# VIP.net
KiCad netlist of a schematic drawn in EAGLE
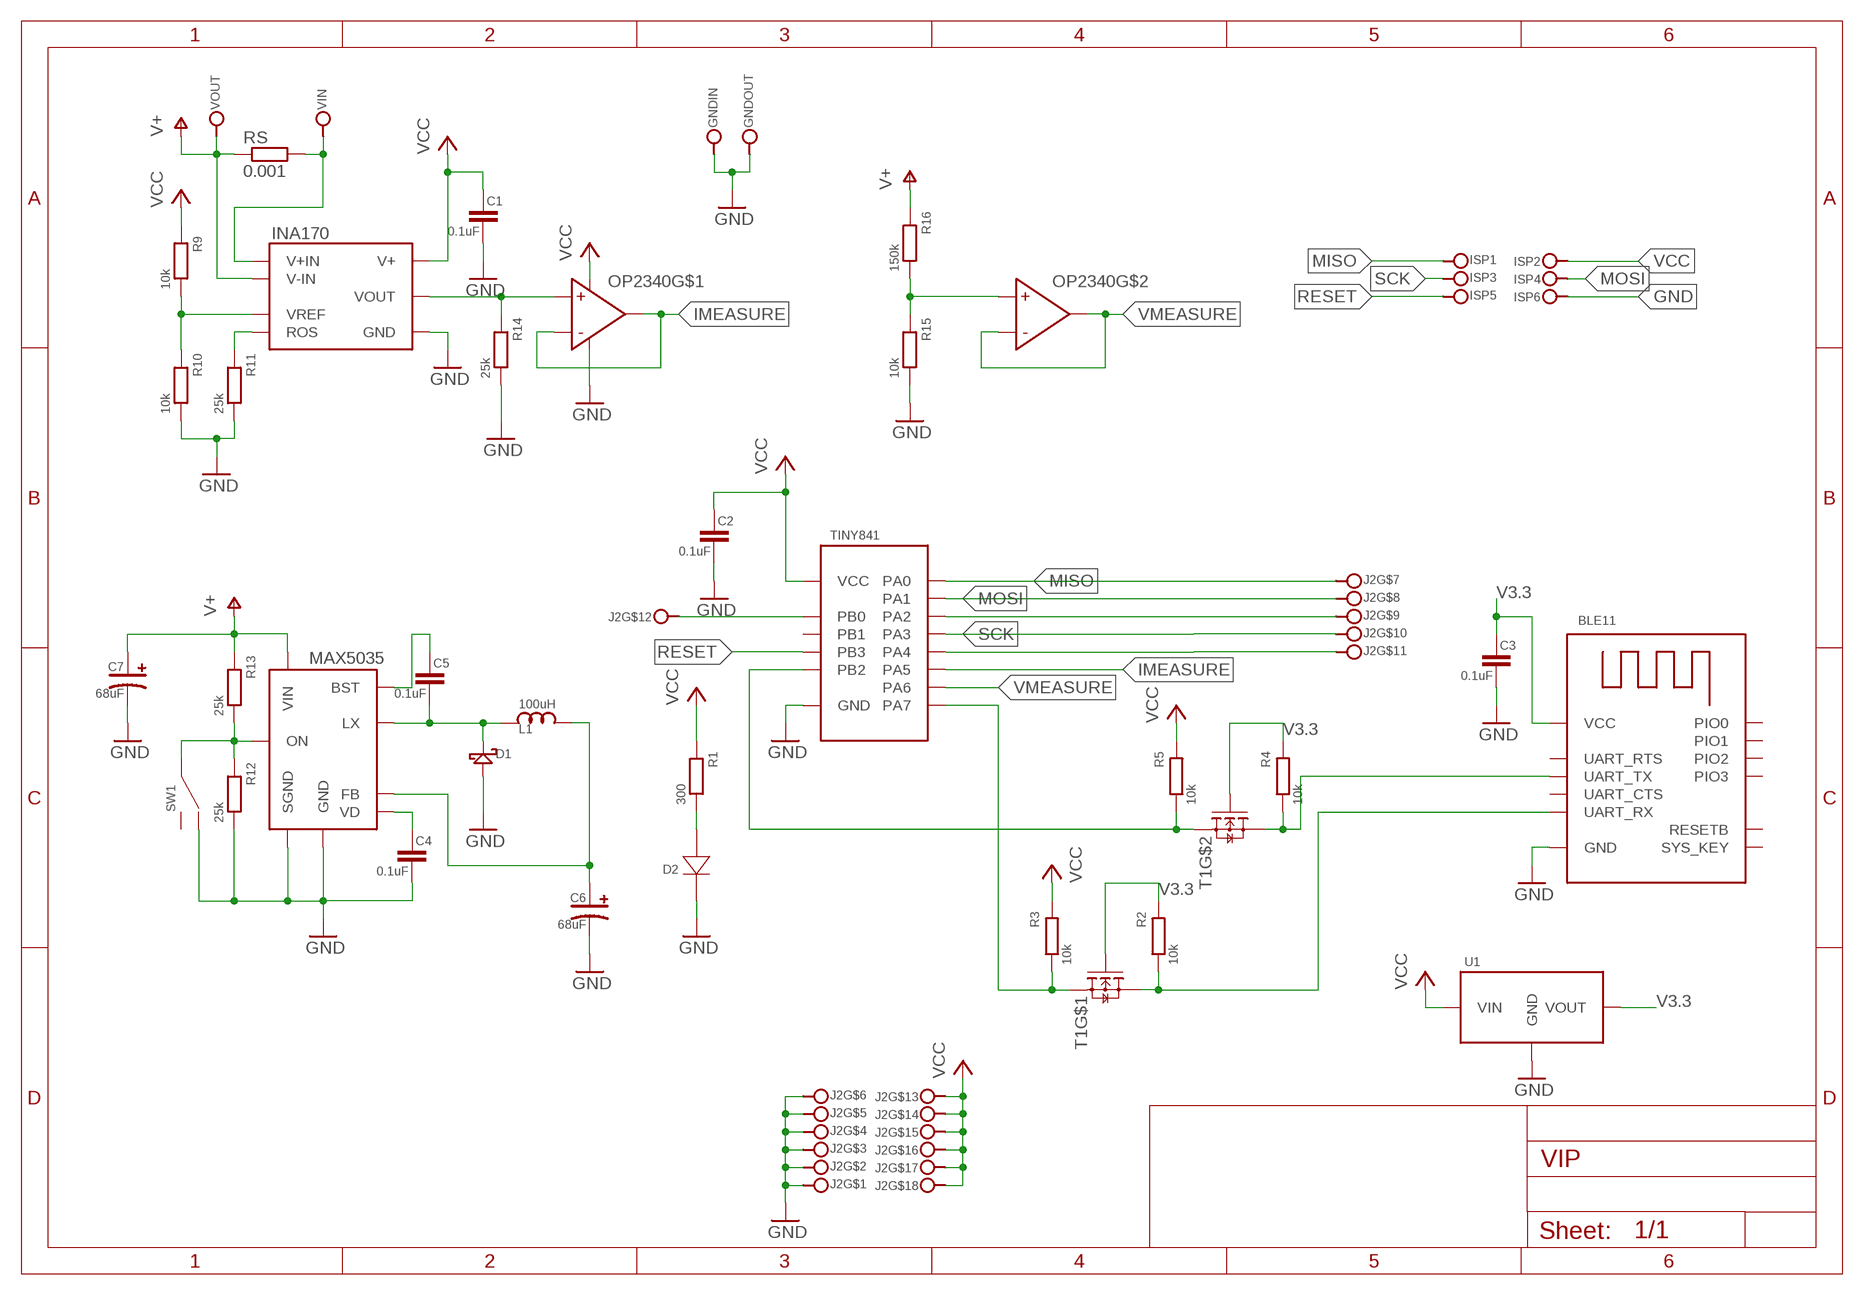
[diagram p0: schematic, sheet 1]

(export (version "E")
  (design (tool "Eeschema 10.0.6"))
  (components
    (comp (ref "BLE11")
      (value "HM-17BLE")
      (footprint "eagle-import:HM17BLE")
      (libsource (lib "eagle-import") (part "HM-17BLE"))
    )
    (comp (ref "C1")
      (value "0.1uF")
      (footprint "eagle-import:0603L")
      (libsource (lib "eagle-import") (part "C_SMD"))
    )
    (comp (ref "C2")
      (value "0.1uF")
      (footprint "eagle-import:0603L")
      (libsource (lib "eagle-import") (part "C_SMD"))
    )
    (comp (ref "C3")
      (value "0.1uF")
      (footprint "eagle-import:0603L")
      (libsource (lib "eagle-import") (part "C_SMD"))
    )
    (comp (ref "C4")
      (value "0.1uF")
      (footprint "eagle-import:0603L")
      (libsource (lib "eagle-import") (part "C_SMD"))
    )
    (comp (ref "C5")
      (value "0.1uF")
      (footprint "eagle-import:0603L")
      (libsource (lib "eagle-import") (part "C_SMD"))
    )
    (comp (ref "C6")
      (value "68uF")
      (footprint "eagle-import:RAD6.3MM")
      (libsource (lib "eagle-import") (part "ECAP_SMD6.3MM"))
    )
    (comp (ref "C7")
      (value "68uF")
      (footprint "eagle-import:RAD12.5MM")
      (libsource (lib "eagle-import") (part "ECAP_SMD12.5MM"))
    )
    (comp (ref "D1")
      (value "SCHOTTKY")
      (footprint "eagle-import:DO-214AA")
      (libsource (lib "eagle-import") (part "SCHOTTKY"))
    )
    (comp (ref "D2")
      (value "SINGLELEDKP-3216SRC-PRV")
      (footprint "eagle-import:LED3.2X1.6MM")
      (libsource (lib "eagle-import") (part "SINGLELEDKP-3216SRC-PRV"))
    )
    (comp (ref "GNDIN")
      (value "POWERTAB")
      (footprint "eagle-import:POWER8X10MM")
      (libsource (lib "eagle-import") (part "POWERTAB"))
    )
    (comp (ref "GNDOUT")
      (value "POWERTAB")
      (footprint "eagle-import:POWER8X10MM")
      (libsource (lib "eagle-import") (part "POWERTAB"))
    )
    (comp (ref "INA170")
      (value "INA170")
      (footprint "eagle-import:INA170")
      (libsource (lib "eagle-import") (part "INA170"))
    )
    (comp (ref "ISP")
      (value "CON254_6WAY254-2X3-EDGE")
      (footprint "eagle-import:CON254MM08_2X3_EDGE")
      (libsource (lib "eagle-import") (part "CON254_6WAY254-2X3-EDGE"))
    )
    (comp (ref "J2")
      (value "CON254_18WAY3X6")
      (footprint "eagle-import:CON254MM08_3X6")
      (libsource (lib "eagle-import") (part "CON254_18WAY3X6"))
    )
    (comp (ref "L1")
      (value "100uH")
      (footprint "eagle-import:SRN8040")
      (libsource (lib "eagle-import") (part "L_SMD8040"))
    )
    (comp (ref "MAX5035")
      (value "MAX5035")
      (footprint "eagle-import:NSOIC-8")
      (libsource (lib "eagle-import") (part "MAX5035"))
    )
    (comp (ref "OP2340")
      (value "OPA2340")
      (footprint "eagle-import:SO-8")
      (libsource (lib "eagle-import") (part "OPA2340"))
    )
    (comp (ref "R1")
      (value "300")
      (footprint "eagle-import:0603L")
      (libsource (lib "eagle-import") (part "R_SMD"))
    )
    (comp (ref "R2")
      (value "10k")
      (footprint "eagle-import:0603L")
      (libsource (lib "eagle-import") (part "R_SMD"))
    )
    (comp (ref "R3")
      (value "10k")
      (footprint "eagle-import:0603L")
      (libsource (lib "eagle-import") (part "R_SMD"))
    )
    (comp (ref "R4")
      (value "10k")
      (footprint "eagle-import:0603L")
      (libsource (lib "eagle-import") (part "R_SMD"))
    )
    (comp (ref "R5")
      (value "10k")
      (footprint "eagle-import:0603L")
      (libsource (lib "eagle-import") (part "R_SMD"))
    )
    (comp (ref "R9")
      (value "10k")
      (footprint "eagle-import:0603L")
      (libsource (lib "eagle-import") (part "R_SMD"))
    )
    (comp (ref "R10")
      (value "10k")
      (footprint "eagle-import:0603L")
      (libsource (lib "eagle-import") (part "R_SMD"))
    )
    (comp (ref "R11")
      (value "25k")
      (footprint "eagle-import:0603L")
      (libsource (lib "eagle-import") (part "R_SMD"))
    )
    (comp (ref "R12")
      (value "25k")
      (footprint "eagle-import:0603L")
      (libsource (lib "eagle-import") (part "R_SMD"))
    )
    (comp (ref "R13")
      (value "25k")
      (footprint "eagle-import:0603L")
      (libsource (lib "eagle-import") (part "R_SMD"))
    )
    (comp (ref "R14")
      (value "25k")
      (footprint "eagle-import:0603L")
      (libsource (lib "eagle-import") (part "R_SMD"))
    )
    (comp (ref "R15")
      (value "10k")
      (footprint "eagle-import:0603L")
      (libsource (lib "eagle-import") (part "R_SMD"))
    )
    (comp (ref "R16")
      (value "150k")
      (footprint "eagle-import:0603L")
      (libsource (lib "eagle-import") (part "R_SMD"))
    )
    (comp (ref "RS")
      (value "0.001")
      (footprint "eagle-import:3921[1052METRIC]")
      (libsource (lib "eagle-import") (part "R-EU_3921[1052METRIC]"))
    )
    (comp (ref "SW1")
      (value "SWITCH-1P2T")
      (footprint "eagle-import:JS102011")
      (libsource (lib "eagle-import") (part "SWITCH-1P2T"))
    )
    (comp (ref "T1")
      (value "2N7002")
      (footprint "eagle-import:SOT-563")
      (libsource (lib "eagle-import") (part "2N7002"))
    )
    (comp (ref "TINY841")
      (value "ATTINY841")
      (footprint "eagle-import:SOIC14")
      (libsource (lib "eagle-import") (part "ATTINY841"))
    )
    (comp (ref "U1")
      (value "L78L33A")
      (footprint "eagle-import:SOT-89")
      (libsource (lib "eagle-import") (part "L78L33A"))
    )
    (comp (ref "VIN")
      (value "POWERTAB")
      (footprint "eagle-import:POWER8X10MM")
      (libsource (lib "eagle-import") (part "POWERTAB"))
    )
    (comp (ref "VOUT")
      (value "POWERTAB")
      (footprint "eagle-import:POWER8X10MM")
      (libsource (lib "eagle-import") (part "POWERTAB"))
    )
  )
  (nets
    (net (code "1") (name "/V3.3") (class "Default")
      (node (ref "BLE11") (pin "P$9") (pinfunction "VCC_P$9") (pintype "bidirectional"))
      (node (ref "C3") (pin "P$1") (pinfunction "P$1_P$1") (pintype "bidirectional"))
      (node (ref "R2") (pin "P$1") (pinfunction "P$1_P$1") (pintype "bidirectional"))
      (node (ref "R4") (pin "P$1") (pinfunction "P$1_P$1") (pintype "bidirectional"))
      (node (ref "T1") (pin "P$2") (pinfunction "G_P$2") (pintype "bidirectional"))
      (node (ref "T1") (pin "P$5") (pinfunction "G_P$5") (pintype "bidirectional"))
      (node (ref "U1") (pin "P$1") (pinfunction "VOUT_P$1") (pintype "bidirectional"))
    )
    (net (code "2") (name "GND") (class "Default")
      (node (ref "BLE11") (pin "P$12") (pinfunction "GND_P$12") (pintype "bidirectional"))
      (node (ref "C1") (pin "P$2") (pinfunction "P$2_P$2") (pintype "bidirectional"))
      (node (ref "C2") (pin "P$2") (pinfunction "P$2_P$2") (pintype "bidirectional"))
      (node (ref "C3") (pin "P$2") (pinfunction "P$2_P$2") (pintype "bidirectional"))
      (node (ref "C4") (pin "P$2") (pinfunction "P$2_P$2") (pintype "bidirectional"))
      (node (ref "C6") (pin "P$2") (pinfunction "P$2_P$2") (pintype "bidirectional"))
      (node (ref "C7") (pin "P$2") (pinfunction "P$2_P$2") (pintype "bidirectional"))
      (node (ref "D1") (pin "P$2") (pinfunction "A_P$2") (pintype "bidirectional"))
      (node (ref "D2") (pin "P$2") (pinfunction "K_P$2") (pintype "bidirectional"))
      (node (ref "GNDIN") (pin "P$1") (pinfunction "J$1_P$1") (pintype "bidirectional"))
      (node (ref "GNDOUT") (pin "P$1") (pinfunction "J$1_P$1") (pintype "bidirectional"))
      (node (ref "INA170") (pin "P$4") (pinfunction "GND_P$4") (pintype "bidirectional"))
      (node (ref "ISP") (pin "P$6") (pinfunction "J$1_P$6") (pintype "bidirectional"))
      (node (ref "J2") (pin "P$1") (pinfunction "J$1_P$1") (pintype "bidirectional"))
      (node (ref "J2") (pin "P$2") (pinfunction "J$1_P$2") (pintype "bidirectional"))
      (node (ref "J2") (pin "P$3") (pinfunction "J$1_P$3") (pintype "bidirectional"))
      (node (ref "J2") (pin "P$4") (pinfunction "J$1_P$4") (pintype "bidirectional"))
      (node (ref "J2") (pin "P$5") (pinfunction "J$1_P$5") (pintype "bidirectional"))
      (node (ref "J2") (pin "P$6") (pinfunction "J$1_P$6") (pintype "bidirectional"))
      (node (ref "MAX5035") (pin "P$3") (pinfunction "SGND_P$3") (pintype "bidirectional"))
      (node (ref "MAX5035") (pin "P$6") (pinfunction "GND_P$6") (pintype "bidirectional"))
      (node (ref "OP2340") (pin "P$4") (pinfunction "V-_P$4") (pintype "power_in"))
      (node (ref "R10") (pin "P$2") (pinfunction "P$2_P$2") (pintype "bidirectional"))
      (node (ref "R11") (pin "P$2") (pinfunction "P$2_P$2") (pintype "bidirectional"))
      (node (ref "R12") (pin "P$2") (pinfunction "P$2_P$2") (pintype "bidirectional"))
      (node (ref "R14") (pin "P$2") (pinfunction "P$2_P$2") (pintype "bidirectional"))
      (node (ref "R15") (pin "P$2") (pinfunction "P$2_P$2") (pintype "bidirectional"))
      (node (ref "SW1") (pin "P$1") (pinfunction "P$2_P$1") (pintype "bidirectional"))
      (node (ref "TINY841") (pin "P$14") (pinfunction "GND_P$14") (pintype "bidirectional"))
      (node (ref "U1") (pin "P$2") (pinfunction "GND_P$2") (pintype "bidirectional"))
    )
    (net (code "3") (name "IMEASURE") (class "Default")
      (node (ref "OP2340") (pin "P$1") (pinfunction "OUT_P$1") (pintype "bidirectional"))
      (node (ref "OP2340") (pin "P$2") (pinfunction "IN-_P$2") (pintype "bidirectional"))
      (node (ref "TINY841") (pin "P$8") (pinfunction "PA5_P$8") (pintype "bidirectional"))
    )
    (net (code "4") (name "MISO") (class "Default")
      (node (ref "ISP") (pin "P$1") (pinfunction "J$1_P$1") (pintype "bidirectional"))
      (node (ref "J2") (pin "P$7") (pinfunction "J$1_P$7") (pintype "bidirectional"))
      (node (ref "TINY841") (pin "P$13") (pinfunction "PA0_P$13") (pintype "bidirectional"))
    )
    (net (code "5") (name "MOSI") (class "Default")
      (node (ref "ISP") (pin "P$4") (pinfunction "J$1_P$4") (pintype "bidirectional"))
      (node (ref "J2") (pin "P$8") (pinfunction "J$1_P$8") (pintype "bidirectional"))
      (node (ref "TINY841") (pin "P$12") (pinfunction "PA1_P$12") (pintype "bidirectional"))
    )
    (net (code "6") (name "Net-(BLE11-UART_RX)") (class "Default")
      (node (ref "BLE11") (pin "P$4") (pinfunction "UART_RX_P$4") (pintype "bidirectional"))
      (node (ref "R2") (pin "P$2") (pinfunction "P$2_P$2") (pintype "bidirectional"))
      (node (ref "T1") (pin "P$3") (pinfunction "D_P$3") (pintype "bidirectional"))
    )
    (net (code "7") (name "Net-(BLE11-UART_TX)") (class "Default")
      (node (ref "BLE11") (pin "P$2") (pinfunction "UART_TX_P$2") (pintype "bidirectional"))
      (node (ref "R4") (pin "P$2") (pinfunction "P$2_P$2") (pintype "bidirectional"))
      (node (ref "T1") (pin "P$6") (pinfunction "D_P$6") (pintype "bidirectional"))
    )
    (net (code "8") (name "Net-(D1-C)") (class "Default")
      (node (ref "C5") (pin "P$2") (pinfunction "P$2_P$2") (pintype "bidirectional"))
      (node (ref "D1") (pin "P$1") (pinfunction "C_P$1") (pintype "bidirectional"))
      (node (ref "L1") (pin "P$1") (pinfunction "P$1_P$1") (pintype "bidirectional"))
      (node (ref "MAX5035") (pin "P$8") (pinfunction "LX_P$8") (pintype "bidirectional"))
    )
    (net (code "9") (name "Net-(D2-A)") (class "Default")
      (node (ref "D2") (pin "P$1") (pinfunction "A_P$1") (pintype "bidirectional"))
      (node (ref "R1") (pin "P$2") (pinfunction "P$2_P$2") (pintype "bidirectional"))
    )
    (net (code "10") (name "Net-(INA170-ROS)") (class "Default")
      (node (ref "INA170") (pin "P$5") (pinfunction "ROS_P$5") (pintype "bidirectional"))
      (node (ref "R11") (pin "P$1") (pinfunction "P$1_P$1") (pintype "bidirectional"))
    )
    (net (code "11") (name "Net-(INA170-V+IN)") (class "Default")
      (node (ref "INA170") (pin "P$2") (pinfunction "V+IN_P$2") (pintype "bidirectional"))
      (node (ref "RS") (pin "P$2") (pinfunction "2_P$2") (pintype "passive"))
      (node (ref "VIN") (pin "P$1") (pinfunction "J$1_P$1") (pintype "bidirectional"))
    )
    (net (code "12") (name "Net-(INA170-VOUT)") (class "Default")
      (node (ref "INA170") (pin "P$6") (pinfunction "VOUT_P$6") (pintype "bidirectional"))
      (node (ref "OP2340") (pin "P$3") (pinfunction "IN+_P$3") (pintype "bidirectional"))
      (node (ref "R14") (pin "P$1") (pinfunction "P$1_P$1") (pintype "bidirectional"))
    )
    (net (code "13") (name "Net-(INA170-VREF)") (class "Default")
      (node (ref "INA170") (pin "P$3") (pinfunction "VREF_P$3") (pintype "bidirectional"))
      (node (ref "R10") (pin "P$1") (pinfunction "P$1_P$1") (pintype "bidirectional"))
      (node (ref "R9") (pin "P$2") (pinfunction "P$2_P$2") (pintype "bidirectional"))
    )
    (net (code "14") (name "Net-(J2C-J$1)") (class "Default")
      (node (ref "J2") (pin "P$11") (pinfunction "J$1_P$11") (pintype "bidirectional"))
      (node (ref "TINY841") (pin "P$9") (pinfunction "PA4_P$9") (pintype "bidirectional"))
    )
    (net (code "15") (name "Net-(J2D-J$1)") (class "Default")
      (node (ref "J2") (pin "P$12") (pinfunction "J$1_P$12") (pintype "bidirectional"))
      (node (ref "TINY841") (pin "P$2") (pinfunction "PB0_P$2") (pintype "bidirectional"))
    )
    (net (code "16") (name "Net-(J2R-J$1)") (class "Default")
      (node (ref "J2") (pin "P$9") (pinfunction "J$1_P$9") (pintype "bidirectional"))
      (node (ref "TINY841") (pin "P$11") (pinfunction "PA2_P$11") (pintype "bidirectional"))
    )
    (net (code "17") (name "Net-(MAX5035-BST)") (class "Default")
      (node (ref "C5") (pin "P$1") (pinfunction "P$1_P$1") (pintype "bidirectional"))
      (node (ref "MAX5035") (pin "P$1") (pinfunction "BST_P$1") (pintype "bidirectional"))
    )
    (net (code "18") (name "Net-(MAX5035-FB)") (class "Default")
      (node (ref "C6") (pin "P$1") (pinfunction "P$1_P$1") (pintype "bidirectional"))
      (node (ref "L1") (pin "P$2") (pinfunction "P$2_P$2") (pintype "bidirectional"))
      (node (ref "MAX5035") (pin "P$4") (pinfunction "FB_P$4") (pintype "bidirectional"))
    )
    (net (code "19") (name "Net-(MAX5035-ON)") (class "Default")
      (node (ref "MAX5035") (pin "P$5") (pinfunction "ON_P$5") (pintype "bidirectional"))
      (node (ref "R12") (pin "P$1") (pinfunction "P$1_P$1") (pintype "bidirectional"))
      (node (ref "R13") (pin "P$2") (pinfunction "P$2_P$2") (pintype "bidirectional"))
      (node (ref "SW1") (pin "P$2") (pinfunction "P$1_P$2") (pintype "bidirectional"))
    )
    (net (code "20") (name "Net-(MAX5035-VD)") (class "Default")
      (node (ref "C4") (pin "P$1") (pinfunction "P$1_P$1") (pintype "bidirectional"))
      (node (ref "MAX5035") (pin "P$2") (pinfunction "VD_P$2") (pintype "bidirectional"))
    )
    (net (code "21") (name "Net-(OP2340B-IN+)") (class "Default")
      (node (ref "OP2340") (pin "P$5") (pinfunction "IN+_P$5") (pintype "bidirectional"))
      (node (ref "R15") (pin "P$1") (pinfunction "P$1_P$1") (pintype "bidirectional"))
      (node (ref "R16") (pin "P$2") (pinfunction "P$2_P$2") (pintype "bidirectional"))
    )
    (net (code "22") (name "Net-(T1A-S)") (class "Default")
      (node (ref "R3") (pin "P$2") (pinfunction "P$2_P$2") (pintype "bidirectional"))
      (node (ref "T1") (pin "P$4") (pinfunction "S_P$4") (pintype "bidirectional"))
      (node (ref "TINY841") (pin "P$6") (pinfunction "PA7_P$6") (pintype "bidirectional"))
    )
    (net (code "23") (name "Net-(T1B-S)") (class "Default")
      (node (ref "R5") (pin "P$2") (pinfunction "P$2_P$2") (pintype "bidirectional"))
      (node (ref "T1") (pin "P$1") (pinfunction "S_P$1") (pintype "bidirectional"))
      (node (ref "TINY841") (pin "P$5") (pinfunction "PB2_P$5") (pintype "bidirectional"))
    )
    (net (code "24") (name "RESET") (class "Default")
      (node (ref "ISP") (pin "P$5") (pinfunction "J$1_P$5") (pintype "bidirectional"))
      (node (ref "TINY841") (pin "P$4") (pinfunction "PB3_P$4") (pintype "bidirectional"))
    )
    (net (code "25") (name "SCK") (class "Default")
      (node (ref "ISP") (pin "P$3") (pinfunction "J$1_P$3") (pintype "bidirectional"))
      (node (ref "J2") (pin "P$10") (pinfunction "J$1_P$10") (pintype "bidirectional"))
      (node (ref "TINY841") (pin "P$10") (pinfunction "PA3_P$10") (pintype "bidirectional"))
    )
    (net (code "26") (name "V+") (class "Default")
      (node (ref "C7") (pin "P$1") (pinfunction "P$1_P$1") (pintype "bidirectional"))
      (node (ref "INA170") (pin "P$1") (pinfunction "V-IN_P$1") (pintype "bidirectional"))
      (node (ref "MAX5035") (pin "P$7") (pinfunction "VIN_P$7") (pintype "bidirectional"))
      (node (ref "R13") (pin "P$1") (pinfunction "P$1_P$1") (pintype "bidirectional"))
      (node (ref "R16") (pin "P$1") (pinfunction "P$1_P$1") (pintype "bidirectional"))
      (node (ref "RS") (pin "P$1") (pinfunction "1_P$1") (pintype "passive"))
      (node (ref "VOUT") (pin "P$1") (pinfunction "J$1_P$1") (pintype "bidirectional"))
    )
    (net (code "27") (name "VCC") (class "Default")
      (node (ref "C1") (pin "P$1") (pinfunction "P$1_P$1") (pintype "bidirectional"))
      (node (ref "C2") (pin "P$1") (pinfunction "P$1_P$1") (pintype "bidirectional"))
      (node (ref "INA170") (pin "P$8") (pinfunction "V+_P$8") (pintype "bidirectional"))
      (node (ref "ISP") (pin "P$2") (pinfunction "J$1_P$2") (pintype "bidirectional"))
      (node (ref "J2") (pin "P$13") (pinfunction "J$1_P$13") (pintype "bidirectional"))
      (node (ref "J2") (pin "P$14") (pinfunction "J$1_P$14") (pintype "bidirectional"))
      (node (ref "J2") (pin "P$15") (pinfunction "J$1_P$15") (pintype "bidirectional"))
      (node (ref "J2") (pin "P$16") (pinfunction "J$1_P$16") (pintype "bidirectional"))
      (node (ref "J2") (pin "P$17") (pinfunction "J$1_P$17") (pintype "bidirectional"))
      (node (ref "J2") (pin "P$18") (pinfunction "J$1_P$18") (pintype "bidirectional"))
      (node (ref "OP2340") (pin "P$8") (pinfunction "V+_P$8") (pintype "power_in"))
      (node (ref "R1") (pin "P$1") (pinfunction "P$1_P$1") (pintype "bidirectional"))
      (node (ref "R3") (pin "P$1") (pinfunction "P$1_P$1") (pintype "bidirectional"))
      (node (ref "R5") (pin "P$1") (pinfunction "P$1_P$1") (pintype "bidirectional"))
      (node (ref "R9") (pin "P$1") (pinfunction "P$1_P$1") (pintype "bidirectional"))
      (node (ref "TINY841") (pin "P$1") (pinfunction "VCC_P$1") (pintype "bidirectional"))
      (node (ref "U1") (pin "P$3") (pinfunction "VIN_P$3") (pintype "bidirectional"))
    )
    (net (code "28") (name "VMEASURE") (class "Default")
      (node (ref "OP2340") (pin "P$6") (pinfunction "IN-_P$6") (pintype "bidirectional"))
      (node (ref "OP2340") (pin "P$7") (pinfunction "OUT_P$7") (pintype "bidirectional"))
      (node (ref "TINY841") (pin "P$7") (pinfunction "PA6_P$7") (pintype "bidirectional"))
    )
    (net (code "29") (name "unconnected-(BLE11-PIO0-PadP$16)") (class "Default")
      (node (ref "BLE11") (pin "P$16") (pinfunction "PIO0_P$16") (pintype "bidirectional"))
    )
    (net (code "30") (name "unconnected-(BLE11-PIO1-PadP$15)") (class "Default")
      (node (ref "BLE11") (pin "P$15") (pinfunction "PIO1_P$15") (pintype "bidirectional"))
    )
    (net (code "31") (name "unconnected-(BLE11-PIO2-PadP$14)") (class "Default")
      (node (ref "BLE11") (pin "P$14") (pinfunction "PIO2_P$14") (pintype "bidirectional"))
    )
    (net (code "32") (name "unconnected-(BLE11-PIO3-PadP$13)") (class "Default")
      (node (ref "BLE11") (pin "P$13") (pinfunction "PIO3_P$13") (pintype "bidirectional"))
    )
    (net (code "33") (name "unconnected-(BLE11-RESETB-PadP$11)") (class "Default")
      (node (ref "BLE11") (pin "P$11") (pinfunction "RESETB_P$11") (pintype "bidirectional"))
    )
    (net (code "34") (name "unconnected-(BLE11-SYS_KEY-PadP$8)") (class "Default")
      (node (ref "BLE11") (pin "P$8") (pinfunction "SYS_KEY_P$8") (pintype "bidirectional"))
    )
    (net (code "35") (name "unconnected-(BLE11-UART_CTS-PadP$3)") (class "Default")
      (node (ref "BLE11") (pin "P$3") (pinfunction "UART_CTS_P$3") (pintype "bidirectional"))
    )
    (net (code "36") (name "unconnected-(BLE11-UART_RTS-PadP$1)") (class "Default")
      (node (ref "BLE11") (pin "P$1") (pinfunction "UART_RTS_P$1") (pintype "bidirectional"))
    )
    (net (code "37") (name "unconnected-(SW1-PadP$3)") (class "Default")
      (node (ref "SW1") (pin "P$3") (pinfunction "P$3_P$3") (pintype "bidirectional"))
    )
    (net (code "38") (name "unconnected-(TINY841-PB1-PadP$3)") (class "Default")
      (node (ref "TINY841") (pin "P$3") (pinfunction "PB1_P$3") (pintype "bidirectional"))
    )
  )
)
